# SNES_RGBAmp.net
KiCad netlist of a schematic drawn in EAGLE
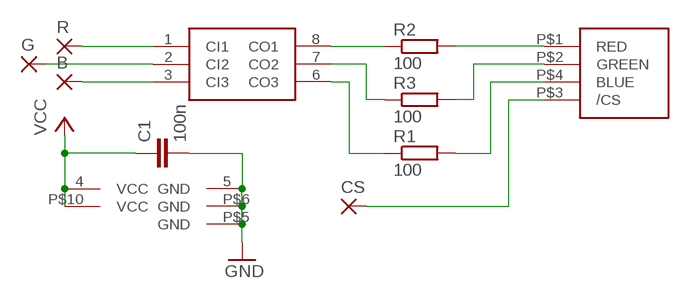
[diagram p0: schematic, sheet 1]

(export (version "E")
  (design (tool "Eeschema 10.0.6"))
  (components
    (comp (ref "B")
      (value "SMD2")
      (footprint "eagle-import:SMD1,27-2,54")
      (libsource (lib "eagle-import") (part "SMD2"))
    )
    (comp (ref "C1")
      (value "100n")
      (footprint "eagle-import:Z0805")
      (libsource (lib "eagle-import") (part "C0805"))
    )
    (comp (ref "CS")
      (value "SMD2")
      (footprint "eagle-import:SMD1,27-2,54")
      (libsource (lib "eagle-import") (part "SMD2"))
    )
    (comp (ref "G")
      (value "SMD2")
      (footprint "eagle-import:SMD1,27-2,54")
      (libsource (lib "eagle-import") (part "SMD2"))
    )
    (comp (ref "R")
      (value "SMD2")
      (footprint "eagle-import:SMD1,27-2,54")
      (libsource (lib "eagle-import") (part "SMD2"))
    )
    (comp (ref "R1")
      (value "100")
      (footprint "eagle-import:Z0805")
      (libsource (lib "eagle-import") (part "R0805"))
    )
    (comp (ref "R2")
      (value "100")
      (footprint "eagle-import:Z0805")
      (libsource (lib "eagle-import") (part "R0805"))
    )
    (comp (ref "R3")
      (value "100")
      (footprint "eagle-import:Z0805")
      (libsource (lib "eagle-import") (part "R0805"))
    )
    (comp (ref "U$1")
      (value "THS7314")
      (footprint "eagle-import:THS7314")
      (libsource (lib "eagle-import") (part "THS7314"))
    )
    (comp (ref "U$3")
      (value "SNES_MULTIAV_RGBC_ONLY")
      (footprint "eagle-import:SNES_MULTIAV_RGBC_ONLY")
      (libsource (lib "eagle-import") (part "SNES_MULTIAV_RGBC_ONLY"))
    )
  )
  (nets
    (net (code "1") (name "GND") (class "Default")
      (node (ref "C1") (pin "2") (pinfunction "2_2") (pintype "passive"))
      (node (ref "U$1") (pin "5") (pinfunction "GND_5") (pintype "bidirectional"))
      (node (ref "U$3") (pin "P$5") (pinfunction "GND_P$5") (pintype "bidirectional"))
      (node (ref "U$3") (pin "P$6") (pinfunction "GND_P$6") (pintype "bidirectional"))
    )
    (net (code "2") (name "Net-(B-P)") (class "Default")
      (node (ref "B") (pin "1") (pinfunction "P_1") (pintype "passive"))
      (node (ref "U$1") (pin "3") (pinfunction "CI3_3") (pintype "bidirectional"))
    )
    (net (code "3") (name "Net-(CS-P)") (class "Default")
      (node (ref "CS") (pin "1") (pinfunction "P_1") (pintype "passive"))
      (node (ref "U$3") (pin "P$3") (pinfunction "/CS_P$3") (pintype "bidirectional"))
    )
    (net (code "4") (name "Net-(G-P)") (class "Default")
      (node (ref "G") (pin "1") (pinfunction "P_1") (pintype "passive"))
      (node (ref "U$1") (pin "2") (pinfunction "CI2_2") (pintype "bidirectional"))
    )
    (net (code "5") (name "Net-(R-P)") (class "Default")
      (node (ref "R") (pin "1") (pinfunction "P_1") (pintype "passive"))
      (node (ref "U$1") (pin "1") (pinfunction "CI1_1") (pintype "bidirectional"))
    )
    (net (code "6") (name "Net-(U$1A-CO1)") (class "Default")
      (node (ref "R2") (pin "1") (pinfunction "1_1") (pintype "passive"))
      (node (ref "U$1") (pin "8") (pinfunction "CO1_8") (pintype "bidirectional"))
    )
    (net (code "7") (name "Net-(U$1A-CO2)") (class "Default")
      (node (ref "R3") (pin "1") (pinfunction "1_1") (pintype "passive"))
      (node (ref "U$1") (pin "7") (pinfunction "CO2_7") (pintype "bidirectional"))
    )
    (net (code "8") (name "Net-(U$1A-CO3)") (class "Default")
      (node (ref "R1") (pin "1") (pinfunction "1_1") (pintype "passive"))
      (node (ref "U$1") (pin "6") (pinfunction "CO3_6") (pintype "bidirectional"))
    )
    (net (code "9") (name "Net-(U$3A-BLUE)") (class "Default")
      (node (ref "R1") (pin "2") (pinfunction "2_2") (pintype "passive"))
      (node (ref "U$3") (pin "P$4") (pinfunction "BLUE_P$4") (pintype "bidirectional"))
    )
    (net (code "10") (name "Net-(U$3A-GREEN)") (class "Default")
      (node (ref "R3") (pin "2") (pinfunction "2_2") (pintype "passive"))
      (node (ref "U$3") (pin "P$2") (pinfunction "GREEN_P$2") (pintype "bidirectional"))
    )
    (net (code "11") (name "Net-(U$3A-RED)") (class "Default")
      (node (ref "R2") (pin "2") (pinfunction "2_2") (pintype "passive"))
      (node (ref "U$3") (pin "P$1") (pinfunction "RED_P$1") (pintype "bidirectional"))
    )
    (net (code "12") (name "VCC") (class "Default")
      (node (ref "C1") (pin "1") (pinfunction "1_1") (pintype "passive"))
      (node (ref "U$1") (pin "4") (pinfunction "VCC_4") (pintype "bidirectional"))
      (node (ref "U$3") (pin "P$10") (pinfunction "VCC_P$10") (pintype "bidirectional"))
    )
  )
)
